# BANK35.net
KiCad netlist of a schematic drawn in Altium Designer
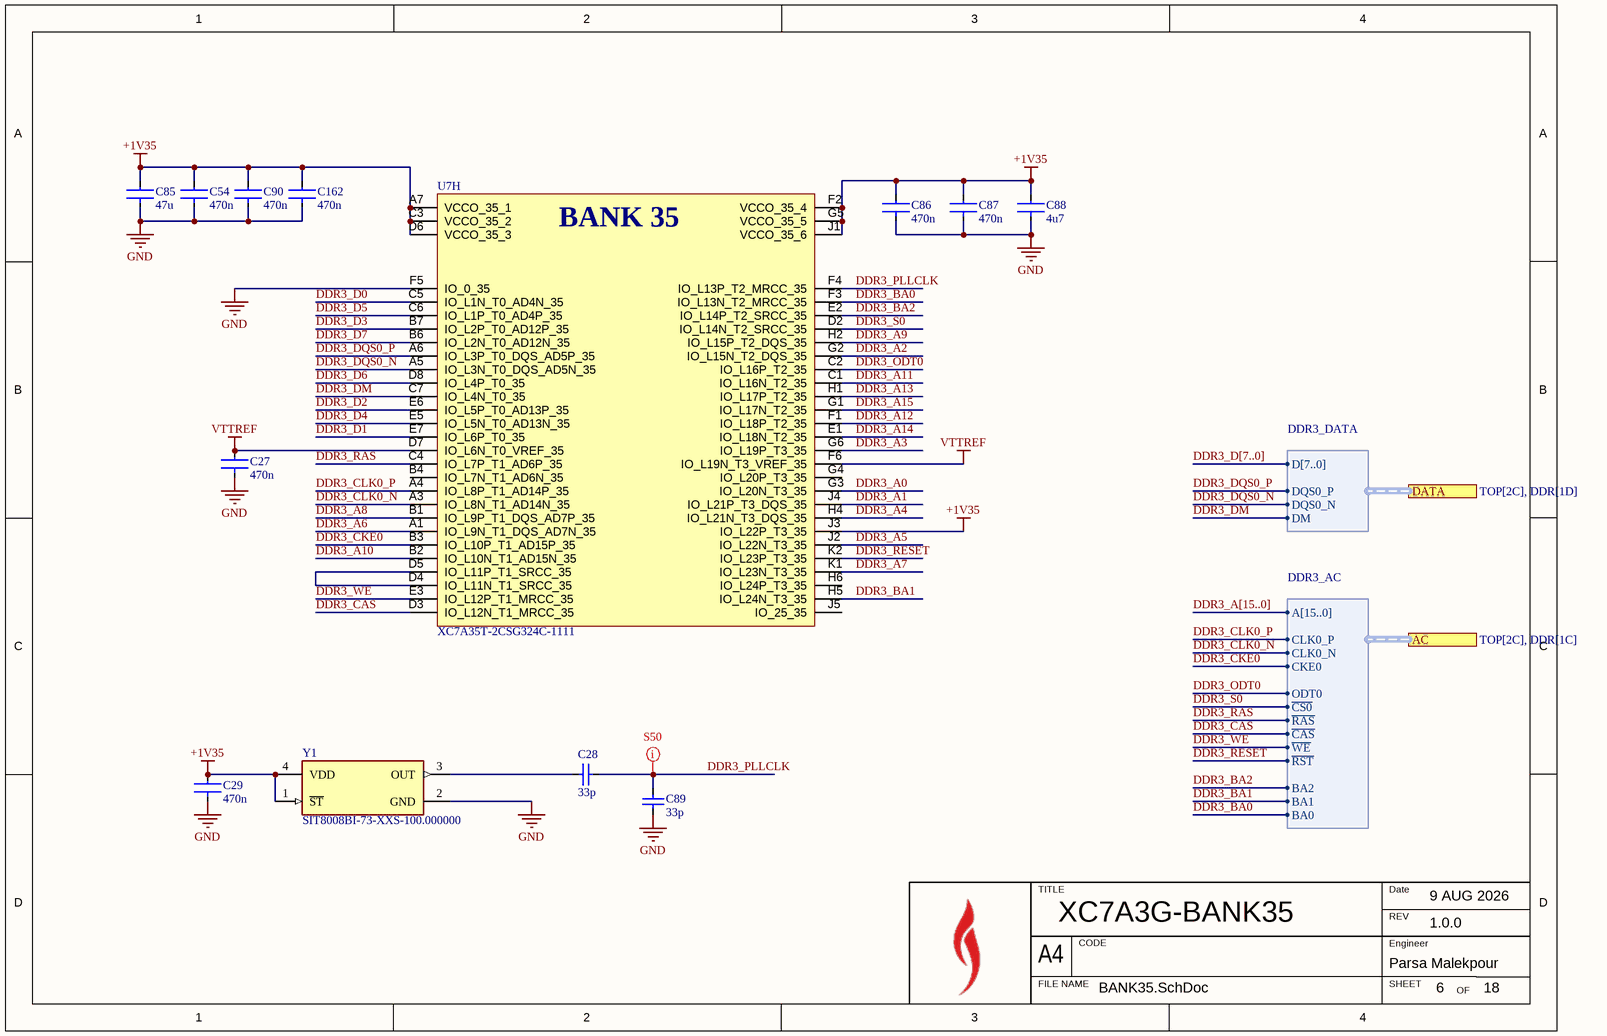
[diagram p0: BANK35.SchDoc]

(export (version "E")
  (design (tool "Eeschema 10.0.6"))
  (components
    (comp (ref "C27")
      (value "470n")
      (footprint "FP-C1005-050-0_05-IPC_C")
      (description "Multilayer Ceramic Capacitors 470nF ±10% 25V X5R SMD 0402")
      (fields (field (name "VOLTAGE") "25V") (field (name "TOLERANCE") "10%"))
      (libsource (lib "Schlib1") (part "b4654b650e69147ec39a6b967a45e02"))
    )
    (comp (ref "C28")
      (value "33p")
      (footprint "FP-C1005-050-0_05-IPC_C")
      (description "Multilayer Ceramic Capacitors 33pF ±5% 50V NP0 SMD 0402")
      (fields (field (name "TOLERANCE") "5%") (field (name "PART NUMBER") "C1005NP01H330J050BA"))
      (libsource (lib "Schlib1") (part "C1005NP01H330J050BA"))
    )
    (comp (ref "C29")
      (value "470n")
      (footprint "FP-C1005-050-0_05-IPC_C")
      (description "Multilayer Ceramic Capacitors 470nF ±10% 25V X5R SMD 0402")
      (fields (field (name "VOLTAGE") "25V") (field (name "TOLERANCE") "10%"))
      (libsource (lib "Schlib1") (part "b4654b650e69147ec39a6b967a45e02"))
    )
    (comp (ref "C54")
      (value "470n")
      (footprint "FP-C1005-050-0_05-IPC_C")
      (description "Multilayer Ceramic Capacitors 470nF ±10% 25V X5R SMD 0402")
      (fields (field (name "VOLTAGE") "25V") (field (name "TOLERANCE") "10%"))
      (libsource (lib "Schlib1") (part "b4654b650e69147ec39a6b967a45e02"))
    )
    (comp (ref "C85")
      (value "47u")
      (footprint "FP-C2012-125-0_2-IPC_C")
      (description "Multilayer Ceramic Capacitors 47μF ±20% 10V X5R SMD 0805")
      (fields (field (name "VOLTAGE") "10V") (field (name "TOLERANCE") "20%"))
      (libsource (lib "Altium Content Vault") (part "b4654b650e69147ec39a6b967a45e02"))
    )
    (comp (ref "C86")
      (value "470n")
      (footprint "FP-C1005-050-0_05-IPC_C")
      (description "Multilayer Ceramic Capacitors 470nF ±10% 25V X5R SMD 0402")
      (fields (field (name "VOLTAGE") "25V") (field (name "TOLERANCE") "10%"))
      (libsource (lib "Schlib1") (part "b4654b650e69147ec39a6b967a45e02"))
    )
    (comp (ref "C87")
      (value "470n")
      (footprint "FP-C1005-050-0_05-IPC_C")
      (description "Multilayer Ceramic Capacitors 470nF ±10% 25V X5R SMD 0402")
      (fields (field (name "VOLTAGE") "25V") (field (name "TOLERANCE") "10%"))
      (libsource (lib "Schlib1") (part "b4654b650e69147ec39a6b967a45e02"))
    )
    (comp (ref "C88")
      (value "4u7")
      (footprint "FP-C1005-050-0_20-0_10-IPC_C")
      (description "CAP CER 4.7UF 10V X5R 0402")
      (fields (field (name "TOLERANCE") "10%") (field (name "PART NUMBER") "C1005X5R1A475K050BE"))
      (libsource (lib "Schlib1") (part "b4654b650e69147ec39a6b967a45e02"))
    )
    (comp (ref "C89")
      (value "33p")
      (footprint "FP-C1005-050-0_05-IPC_C")
      (description "Multilayer Ceramic Capacitors 33pF ±5% 50V NP0 SMD 0402")
      (fields (field (name "TOLERANCE") "5%") (field (name "PART NUMBER") "C1005NP01H330J050BA"))
      (libsource (lib "Schlib1") (part "C1005NP01H330J050BA"))
    )
    (comp (ref "C90")
      (value "470n")
      (footprint "FP-C1005-050-0_05-IPC_C")
      (description "Multilayer Ceramic Capacitors 470nF ±10% 25V X5R SMD 0402")
      (fields (field (name "VOLTAGE") "25V") (field (name "TOLERANCE") "10%"))
      (libsource (lib "Schlib1") (part "b4654b650e69147ec39a6b967a45e02"))
    )
    (comp (ref "C162")
      (value "470n")
      (footprint "FP-C1005-050-0_05-IPC_C")
      (description "Multilayer Ceramic Capacitors 470nF ±10% 25V X5R SMD 0402")
      (fields (field (name "VOLTAGE") "25V") (field (name "TOLERANCE") "10%"))
      (libsource (lib "Schlib1") (part "b4654b650e69147ec39a6b967a45e02"))
    )
    (comp (ref "U7")
      (value "XC7A35T-2CSG324C-1111")
      (footprint "PCBLIB1:BGA324C80P18X18_1500X1500X150")
      (description "Integrated Circuit")
      (fields
        (field (name "MANUFACTURER_PART_NUMBER") "XC7A35T-2CSG324C")
        (field (name "MOUSER PART NUMBER") "217-XC7A35T-2CSG324C")
      )
      (libsource (lib "Schlib1") (part "XC7A35T-2CSG324C-1111"))
    )
    (comp (ref "Y1")
      (value "SIT8008BI-73-XXS-100.000000")
      (footprint "FP-SiT8008-7-MFG")
      (description "MEMS OSC XO 100.0000MHZ HCMOS")
      (libsource (lib "Schlib1") (part "SIT8008BI-73-XXS-100.000000"))
    )
  )
  (nets
    (net (code "3") (name "+1V35") (class "Default")
      (node (ref "C162") (pin "2") (pinfunction "2_2") (pintype "passive"))
      (node (ref "C29") (pin "2") (pinfunction "2_2") (pintype "passive"))
      (node (ref "C54") (pin "2") (pinfunction "2_2") (pintype "passive"))
      (node (ref "C85") (pin "2") (pinfunction "2_2") (pintype "passive"))
      (node (ref "C86") (pin "2") (pinfunction "2_2") (pintype "passive"))
      (node (ref "C87") (pin "2") (pinfunction "2_2") (pintype "passive"))
      (node (ref "C88") (pin "2") (pinfunction "2_2") (pintype "passive"))
      (node (ref "C90") (pin "2") (pinfunction "2_2") (pintype "passive"))
      (node (ref "U7") (pin "A7") (pinfunction "VCCO_35_1_A7") (pintype "passive"))
      (node (ref "U7") (pin "C3") (pinfunction "VCCO_35_2_C3") (pintype "passive"))
      (node (ref "U7") (pin "D6") (pinfunction "VCCO_35_3_D6") (pintype "passive"))
      (node (ref "U7") (pin "F2") (pinfunction "VCCO_35_4_F2") (pintype "passive"))
      (node (ref "U7") (pin "G5") (pinfunction "VCCO_35_5_G5") (pintype "passive"))
      (node (ref "U7") (pin "J1") (pinfunction "VCCO_35_6_J1") (pintype "passive"))
      (node (ref "U7") (pin "J3") (pinfunction "IO_L22P_T3_35_J3") (pintype "passive"))
      (node (ref "Y1") (pin "1") (pinfunction "~{ST}_1") (pintype "input"))
      (node (ref "Y1") (pin "4") (pinfunction "VDD_4") (pintype "power_in"))
    )
    (net (code "4") (name "/DDR3_A0") (class "Default")
      (node (ref "U7") (pin "G3") (pinfunction "IO_L20N_T3_35_G3") (pintype "passive"))
    )
    (net (code "5") (name "/DDR3_A1") (class "Default")
      (node (ref "U7") (pin "J4") (pinfunction "IO_L21P_T3_DQS_35_J4") (pintype "passive"))
    )
    (net (code "6") (name "/DDR3_A2") (class "Default")
      (node (ref "U7") (pin "G2") (pinfunction "IO_L15N_T2_DQS_35_G2") (pintype "passive"))
    )
    (net (code "7") (name "/DDR3_A3") (class "Default")
      (node (ref "U7") (pin "G6") (pinfunction "IO_L19P_T3_35_G6") (pintype "passive"))
    )
    (net (code "8") (name "/DDR3_A4") (class "Default")
      (node (ref "U7") (pin "H4") (pinfunction "IO_L21N_T3_DQS_35_H4") (pintype "passive"))
    )
    (net (code "9") (name "/DDR3_A5") (class "Default")
      (node (ref "U7") (pin "J2") (pinfunction "IO_L22N_T3_35_J2") (pintype "passive"))
    )
    (net (code "10") (name "/DDR3_A6") (class "Default")
      (node (ref "U7") (pin "A1") (pinfunction "IO_L9N_T1_DQS_AD7N_35_A1") (pintype "passive"))
    )
    (net (code "11") (name "/DDR3_A7") (class "Default")
      (node (ref "U7") (pin "K1") (pinfunction "IO_L23N_T3_35_K1") (pintype "passive"))
    )
    (net (code "12") (name "/DDR3_A8") (class "Default")
      (node (ref "U7") (pin "B1") (pinfunction "IO_L9P_T1_DQS_AD7P_35_B1") (pintype "passive"))
    )
    (net (code "13") (name "/DDR3_A9") (class "Default")
      (node (ref "U7") (pin "H2") (pinfunction "IO_L15P_T2_DQS_35_H2") (pintype "passive"))
    )
    (net (code "14") (name "/DDR3_A10") (class "Default")
      (node (ref "U7") (pin "B2") (pinfunction "IO_L10N_T1_AD15N_35_B2") (pintype "passive"))
    )
    (net (code "15") (name "/DDR3_A11") (class "Default")
      (node (ref "U7") (pin "C1") (pinfunction "IO_L16N_T2_35_C1") (pintype "passive"))
    )
    (net (code "16") (name "/DDR3_A12") (class "Default")
      (node (ref "U7") (pin "F1") (pinfunction "IO_L18P_T2_35_F1") (pintype "passive"))
    )
    (net (code "17") (name "/DDR3_A13") (class "Default")
      (node (ref "U7") (pin "H1") (pinfunction "IO_L17P_T2_35_H1") (pintype "passive"))
    )
    (net (code "18") (name "/DDR3_A14") (class "Default")
      (node (ref "U7") (pin "E1") (pinfunction "IO_L18N_T2_35_E1") (pintype "passive"))
    )
    (net (code "19") (name "/DDR3_A15") (class "Default")
      (node (ref "U7") (pin "G1") (pinfunction "IO_L17N_T2_35_G1") (pintype "passive"))
    )
    (net (code "21") (name "/DDR3_BA0") (class "Default")
      (node (ref "U7") (pin "F3") (pinfunction "IO_L13N_T2_MRCC_35_F3") (pintype "passive"))
    )
    (net (code "22") (name "/DDR3_BA1") (class "Default")
      (node (ref "U7") (pin "H5") (pinfunction "IO_L24N_T3_35_H5") (pintype "passive"))
    )
    (net (code "23") (name "/DDR3_BA2") (class "Default")
      (node (ref "U7") (pin "E2") (pinfunction "IO_L14P_T2_SRCC_35_E2") (pintype "passive"))
    )
    (net (code "24") (name "/DDR3_CAS") (class "Default")
      (node (ref "U7") (pin "D3") (pinfunction "IO_L12N_T1_MRCC_35_D3") (pintype "passive"))
    )
    (net (code "25") (name "/DDR3_CKE0") (class "Default")
      (node (ref "U7") (pin "B3") (pinfunction "IO_L10P_T1_AD15P_35_B3") (pintype "passive"))
    )
    (net (code "26") (name "/DDR3_CLK0_N") (class "Default")
      (node (ref "U7") (pin "A3") (pinfunction "IO_L8N_T1_AD14N_35_A3") (pintype "passive"))
    )
    (net (code "27") (name "/DDR3_CLK0_P") (class "Default")
      (node (ref "U7") (pin "A4") (pinfunction "IO_L8P_T1_AD14P_35_A4") (pintype "passive"))
    )
    (net (code "28") (name "/DDR3_D0") (class "Default")
      (node (ref "U7") (pin "C5") (pinfunction "IO_L1N_T0_AD4N_35_C5") (pintype "passive"))
    )
    (net (code "29") (name "/DDR3_D1") (class "Default")
      (node (ref "U7") (pin "E7") (pinfunction "IO_L6P_T0_35_E7") (pintype "passive"))
    )
    (net (code "30") (name "/DDR3_D2") (class "Default")
      (node (ref "U7") (pin "E6") (pinfunction "IO_L5P_T0_AD13P_35_E6") (pintype "passive"))
    )
    (net (code "31") (name "/DDR3_D3") (class "Default")
      (node (ref "U7") (pin "B7") (pinfunction "IO_L2P_T0_AD12P_35_B7") (pintype "passive"))
    )
    (net (code "32") (name "/DDR3_D4") (class "Default")
      (node (ref "U7") (pin "E5") (pinfunction "IO_L5N_T0_AD13N_35_E5") (pintype "passive"))
    )
    (net (code "33") (name "/DDR3_D5") (class "Default")
      (node (ref "U7") (pin "C6") (pinfunction "IO_L1P_T0_AD4P_35_C6") (pintype "passive"))
    )
    (net (code "34") (name "/DDR3_D6") (class "Default")
      (node (ref "U7") (pin "D8") (pinfunction "IO_L4P_T0_35_D8") (pintype "passive"))
    )
    (net (code "35") (name "/DDR3_D7") (class "Default")
      (node (ref "U7") (pin "B6") (pinfunction "IO_L2N_T0_AD12N_35_B6") (pintype "passive"))
    )
    (net (code "36") (name "/DDR3_DM") (class "Default")
      (node (ref "U7") (pin "C7") (pinfunction "IO_L4N_T0_35_C7") (pintype "passive"))
    )
    (net (code "37") (name "/DDR3_DQS0_N") (class "Default")
      (node (ref "U7") (pin "A5") (pinfunction "IO_L3N_T0_DQS_AD5N_35_A5") (pintype "passive"))
    )
    (net (code "38") (name "/DDR3_DQS0_P") (class "Default")
      (node (ref "U7") (pin "A6") (pinfunction "IO_L3P_T0_DQS_AD5P_35_A6") (pintype "passive"))
    )
    (net (code "40") (name "/DDR3_ODT0") (class "Default")
      (node (ref "U7") (pin "C2") (pinfunction "IO_L16P_T2_35_C2") (pintype "passive"))
    )
    (net (code "41") (name "/DDR3_PLLCLK") (class "Default")
      (node (ref "C28") (pin "2") (pinfunction "2_2") (pintype "passive"))
      (node (ref "C89") (pin "2") (pinfunction "2_2") (pintype "passive"))
      (node (ref "U7") (pin "F4") (pinfunction "IO_L13P_T2_MRCC_35_F4") (pintype "passive"))
    )
    (net (code "42") (name "/DDR3_RAS") (class "Default")
      (node (ref "U7") (pin "C4") (pinfunction "IO_L7P_T1_AD6P_35_C4") (pintype "passive"))
    )
    (net (code "43") (name "/DDR3_RESET") (class "Default")
      (node (ref "U7") (pin "K2") (pinfunction "IO_L23P_T3_35_K2") (pintype "passive"))
    )
    (net (code "44") (name "/DDR3_S0") (class "Default")
      (node (ref "U7") (pin "D2") (pinfunction "IO_L14N_T2_SRCC_35_D2") (pintype "passive"))
    )
    (net (code "45") (name "/DDR3_WE") (class "Default")
      (node (ref "U7") (pin "E3") (pinfunction "IO_L12P_T1_MRCC_35_E3") (pintype "passive"))
    )
    (net (code "48") (name "GND") (class "Default")
      (node (ref "C162") (pin "1") (pinfunction "1_1") (pintype "passive"))
      (node (ref "C27") (pin "1") (pinfunction "1_1") (pintype "passive"))
      (node (ref "C29") (pin "1") (pinfunction "1_1") (pintype "passive"))
      (node (ref "C54") (pin "1") (pinfunction "1_1") (pintype "passive"))
      (node (ref "C85") (pin "1") (pinfunction "1_1") (pintype "passive"))
      (node (ref "C86") (pin "1") (pinfunction "1_1") (pintype "passive"))
      (node (ref "C87") (pin "1") (pinfunction "1_1") (pintype "passive"))
      (node (ref "C88") (pin "1") (pinfunction "1_1") (pintype "passive"))
      (node (ref "C89") (pin "1") (pinfunction "1_1") (pintype "passive"))
      (node (ref "C90") (pin "1") (pinfunction "1_1") (pintype "passive"))
      (node (ref "U7") (pin "F5") (pinfunction "IO_0_35_F5") (pintype "passive"))
      (node (ref "Y1") (pin "2") (pinfunction "GND_2") (pintype "power_in"))
    )
    (net (code "49") (name "Net-(U7H-IO_L11N_T1_SRCC_35)") (class "Default")
      (node (ref "U7") (pin "D4") (pinfunction "IO_L11N_T1_SRCC_35_D4") (pintype "passive"))
      (node (ref "U7") (pin "D5") (pinfunction "IO_L11P_T1_SRCC_35_D5") (pintype "passive"))
    )
    (net (code "50") (name "Net-(Y1-OUT)") (class "Default")
      (node (ref "C28") (pin "1") (pinfunction "1_1") (pintype "passive"))
      (node (ref "Y1") (pin "3") (pinfunction "OUT_3") (pintype "output"))
    )
    (net (code "51") (name "VTTREF") (class "Default")
      (node (ref "C27") (pin "2") (pinfunction "2_2") (pintype "passive"))
      (node (ref "U7") (pin "D7") (pinfunction "IO_L6N_T0_VREF_35_D7") (pintype "passive"))
      (node (ref "U7") (pin "F6") (pinfunction "IO_L19N_T3_VREF_35_F6") (pintype "passive"))
    )
    (net (code "52") (name "unconnected-(U7H-IO_25_35-PadJ5)") (class "Default")
      (node (ref "U7") (pin "J5") (pinfunction "IO_25_35_J5") (pintype "passive"))
    )
    (net (code "53") (name "unconnected-(U7H-IO_L7N_T1_AD6N_35-PadB4)") (class "Default")
      (node (ref "U7") (pin "B4") (pinfunction "IO_L7N_T1_AD6N_35_B4") (pintype "passive"))
    )
    (net (code "54") (name "unconnected-(U7H-IO_L20P_T3_35-PadG4)") (class "Default")
      (node (ref "U7") (pin "G4") (pinfunction "IO_L20P_T3_35_G4") (pintype "passive"))
    )
    (net (code "55") (name "unconnected-(U7H-IO_L24P_T3_35-PadH6)") (class "Default")
      (node (ref "U7") (pin "H6") (pinfunction "IO_L24P_T3_35_H6") (pintype "passive"))
    )
  )
)
